# RF_Block.net
KiCad netlist of a schematic drawn in Altium Designer
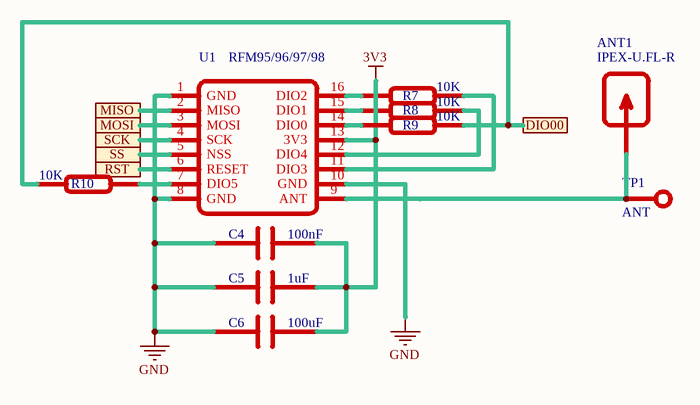
[diagram p0: RF_Block.SchDoc]

(export (version "E")
  (design (tool "Eeschema 10.0.6"))
  (components
    (comp (ref "ANT1")
      (value "IPEX-U.FL-R")
      (footprint "IPEX Connector SMD")
      (description "RF Antena")
      (libsource (lib "CTAI-Library") (part "IPEX-U.FL-R"))
    )
    (comp (ref "C4")
      (value "100nF")
      (footprint "C0805")
      (description "Ceramic Capacitor")
      (libsource (lib "CTAI-Library") (part "CAP-CER"))
    )
    (comp (ref "C5")
      (value "1uF")
      (footprint "C0805")
      (description "Ceramic Capacitor")
      (libsource (lib "CTAI-Library") (part "CAP-CER"))
    )
    (comp (ref "C6")
      (value "100uF")
      (footprint "C0805")
      (description "Ceramic Capacitor")
      (libsource (lib "CTAI-Library") (part "CAP-CER"))
    )
    (comp (ref "R7")
      (value "10K")
      (footprint "R0805")
      (description "Resistor")
      (libsource (lib "CTAI-Library") (part "Resistor"))
    )
    (comp (ref "R8")
      (value "10K")
      (footprint "R0805")
      (description "Resistor")
      (libsource (lib "CTAI-Library") (part "Resistor"))
    )
    (comp (ref "R9")
      (value "10K")
      (footprint "R0603")
      (description "Resistor")
      (libsource (lib "CTAI-Library") (part "Resistor"))
    )
    (comp (ref "R10")
      (value "10K")
      (footprint "R0603")
      (description "Resistor")
      (libsource (lib "CTAI-Library") (part "Resistor"))
    )
    (comp (ref "TP1")
      (value "ANT")
      (footprint "Test Point")
      (description "Test Point")
      (libsource (lib "CTAI-Library") (part "TestPoint"))
    )
    (comp (ref "U1")
      (value "RFM95/96/97/98")
      (footprint "LORA RFM95/96/97/98W")
      (libsource (lib "CTAI-Library") (part "RFM95/96/97/98 LORA Module"))
    )
  )
  (nets
    (net (code "1") (name "/DIO00") (class "Default")
      (node (ref "R10") (pin "1") (pinfunction "1_1") (pintype "passive"))
      (node (ref "R9") (pin "2") (pinfunction "2_2") (pintype "passive"))
    )
    (net (code "2") (name "/MISO") (class "Default")
      (node (ref "U1") (pin "2") (pinfunction "MISO_2") (pintype "passive"))
    )
    (net (code "3") (name "/MOSI") (class "Default")
      (node (ref "U1") (pin "3") (pinfunction "MOSI_3") (pintype "passive"))
    )
    (net (code "4") (name "/RST") (class "Default")
      (node (ref "U1") (pin "6") (pinfunction "RESET_6") (pintype "passive"))
    )
    (net (code "5") (name "/SCK") (class "Default")
      (node (ref "U1") (pin "4") (pinfunction "SCK_4") (pintype "passive"))
    )
    (net (code "6") (name "/SS") (class "Default")
      (node (ref "U1") (pin "5") (pinfunction "NSS_5") (pintype "passive"))
    )
    (net (code "7") (name "3V3") (class "Default")
      (node (ref "C4") (pin "2") (pintype "passive"))
      (node (ref "C5") (pin "2") (pintype "passive"))
      (node (ref "C6") (pin "2") (pintype "passive"))
      (node (ref "U1") (pin "13") (pinfunction "3V3_13") (pintype "passive"))
    )
    (net (code "8") (name "GND") (class "Default")
      (node (ref "C4") (pin "1") (pintype "passive"))
      (node (ref "C5") (pin "1") (pintype "passive"))
      (node (ref "C6") (pin "1") (pintype "passive"))
      (node (ref "U1") (pin "1") (pinfunction "GND_1") (pintype "passive"))
      (node (ref "U1") (pin "10") (pinfunction "GND_10") (pintype "passive"))
      (node (ref "U1") (pin "8") (pinfunction "GND_8") (pintype "passive"))
    )
    (net (code "9") (name "Net-(U1-ANT)") (class "Default")
      (node (ref "ANT1") (pin "1") (pinfunction "1_1") (pintype "passive"))
      (node (ref "TP1") (pin "1") (pinfunction "1_1") (pintype "passive"))
      (node (ref "U1") (pin "9") (pinfunction "ANT_9") (pintype "passive"))
    )
    (net (code "10") (name "Net-(U1-DIO0)") (class "Default")
      (node (ref "R9") (pin "1") (pinfunction "1_1") (pintype "passive"))
      (node (ref "U1") (pin "14") (pinfunction "DIO0_14") (pintype "passive"))
    )
    (net (code "11") (name "Net-(U1-DIO1)") (class "Default")
      (node (ref "R8") (pin "1") (pinfunction "1_1") (pintype "passive"))
      (node (ref "U1") (pin "15") (pinfunction "DIO1_15") (pintype "passive"))
    )
    (net (code "12") (name "Net-(U1-DIO2)") (class "Default")
      (node (ref "R7") (pin "1") (pinfunction "1_1") (pintype "passive"))
      (node (ref "U1") (pin "16") (pinfunction "DIO2_16") (pintype "passive"))
    )
    (net (code "13") (name "Net-(U1-DIO3)") (class "Default")
      (node (ref "R7") (pin "2") (pinfunction "2_2") (pintype "passive"))
      (node (ref "U1") (pin "11") (pinfunction "DIO3_11") (pintype "passive"))
    )
    (net (code "14") (name "Net-(U1-DIO4)") (class "Default")
      (node (ref "R8") (pin "2") (pinfunction "2_2") (pintype "passive"))
      (node (ref "U1") (pin "12") (pinfunction "DIO4_12") (pintype "passive"))
    )
    (net (code "15") (name "Net-(U1-DIO5)") (class "Default")
      (node (ref "R10") (pin "2") (pinfunction "2_2") (pintype "passive"))
      (node (ref "U1") (pin "7") (pinfunction "DIO5_7") (pintype "passive"))
    )
    (net (code "16") (name "unconnected-(ANT1-GND-Pad2)") (class "Default")
      (node (ref "ANT1") (pin "2") (pinfunction "GND_2") (pintype "passive"))
    )
  )
)
